# Sche.net
KiCad netlist of a schematic drawn in Altium Designer
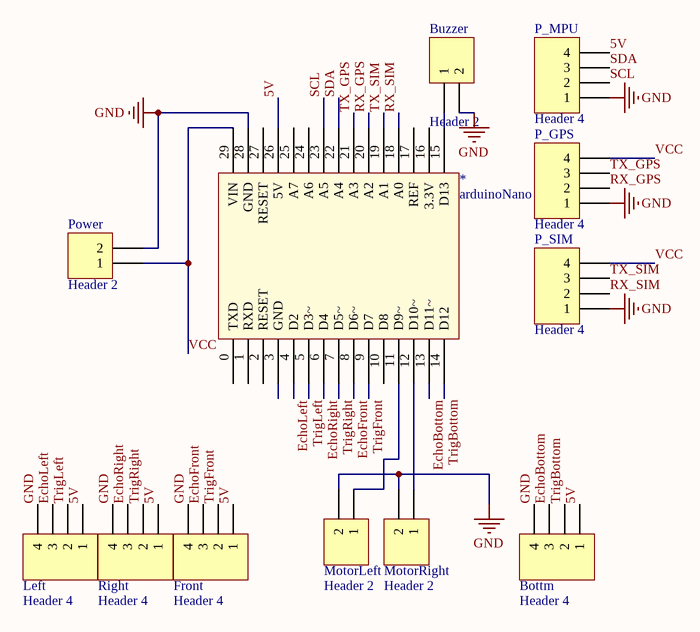
[diagram p0: Sche.SchDoc]

(export (version "E")
  (design (tool "Eeschema 10.0.6"))
  (components
    (comp (ref "*")
      (value "arduinoNano")
      (footprint "Arduino nano")
      (libsource (lib "Duongw_lib") (part "arduinoNano"))
    )
    (comp (ref "Bottm")
      (value "Header 4")
      (footprint "HDR1X4")
      (description "Header, 4-Pin")
      (fields (field (name "PUBLISHER") "Altium Limited"))
      (libsource (lib "") (part "Header 4_1"))
    )
    (comp (ref "Buzzer")
      (value "Header 2")
      (footprint "HDR1X2")
      (description "Header, 2-Pin")
      (fields (field (name "PUBLISHER") "Altium Limited"))
      (libsource (lib "") (part "Header 2_2"))
    )
    (comp (ref "Front")
      (value "Header 4")
      (footprint "HDR1X4")
      (description "Header, 4-Pin")
      (fields (field (name "PUBLISHER") "Altium Limited"))
      (libsource (lib "") (part "Header 4_1"))
    )
    (comp (ref "Left")
      (value "Header 4")
      (footprint "HDR1X4")
      (description "Header, 4-Pin")
      (fields (field (name "PUBLISHER") "Altium Limited"))
      (libsource (lib "") (part "Header 4_1"))
    )
    (comp (ref "MotorLeft")
      (value "Header 2")
      (footprint "HDR1X2")
      (description "Header, 2-Pin")
      (fields (field (name "PUBLISHER") "Altium Limited"))
      (libsource (lib "Miscellaneous Connectors") (part "Header 2"))
    )
    (comp (ref "MotorRight")
      (value "Header 2")
      (footprint "HDR1X2")
      (description "Header, 2-Pin")
      (fields (field (name "PUBLISHER") "Altium Limited"))
      (libsource (lib "Miscellaneous Connectors") (part "Header 2"))
    )
    (comp (ref "Power")
      (value "Header 2")
      (footprint "HDR1X2")
      (description "Header, 2-Pin")
      (fields (field (name "PUBLISHER") "Altium Limited"))
      (libsource (lib "") (part "Header 2_1"))
    )
    (comp (ref "P_GPS")
      (value "Header 4")
      (footprint "HDR1X4")
      (description "Header, 4-Pin")
      (fields (field (name "PUBLISHER") "Altium Limited"))
      (libsource (lib "Miscellaneous Connectors") (part "Header 4"))
    )
    (comp (ref "P_MPU")
      (value "Header 4")
      (footprint "HDR1X4")
      (description "Header, 4-Pin")
      (fields (field (name "PUBLISHER") "Altium Limited"))
      (libsource (lib "Miscellaneous Connectors") (part "Header 4"))
    )
    (comp (ref "P_SIM")
      (value "Header 4")
      (footprint "HDR1X4")
      (description "Header, 4-Pin")
      (fields (field (name "PUBLISHER") "Altium Limited"))
      (libsource (lib "Miscellaneous Connectors") (part "Header 4"))
    )
    (comp (ref "Right")
      (value "Header 4")
      (footprint "HDR1X4")
      (description "Header, 4-Pin")
      (fields (field (name "PUBLISHER") "Altium Limited"))
      (libsource (lib "") (part "Header 4_1"))
    )
  )
  (nets
    (net (code "1") (name "/5V") (class "Default")
      (node (ref "*") (pin "26") (pinfunction "5V_26") (pintype "passive"))
      (node (ref "Bottm") (pin "1") (pinfunction "1_1") (pintype "passive"))
      (node (ref "Front") (pin "1") (pinfunction "1_1") (pintype "passive"))
      (node (ref "Left") (pin "1") (pinfunction "1_1") (pintype "passive"))
      (node (ref "P_MPU") (pin "4") (pinfunction "4_4") (pintype "passive"))
      (node (ref "Right") (pin "1") (pinfunction "1_1") (pintype "passive"))
    )
    (net (code "2") (name "/EchoBottom") (class "Default")
      (node (ref "*") (pin "13") (pinfunction "D11~_13") (pintype "passive"))
      (node (ref "Bottm") (pin "3") (pinfunction "3_3") (pintype "passive"))
    )
    (net (code "3") (name "/EchoFront") (class "Default")
      (node (ref "*") (pin "8") (pinfunction "D6~_8") (pintype "passive"))
      (node (ref "Front") (pin "3") (pinfunction "3_3") (pintype "passive"))
    )
    (net (code "4") (name "/EchoLeft") (class "Default")
      (node (ref "*") (pin "4") (pinfunction "D2_4") (pintype "passive"))
      (node (ref "Left") (pin "3") (pinfunction "3_3") (pintype "passive"))
    )
    (net (code "5") (name "/EchoRight") (class "Default")
      (node (ref "*") (pin "6") (pinfunction "D4_6") (pintype "passive"))
      (node (ref "Right") (pin "3") (pinfunction "3_3") (pintype "passive"))
    )
    (net (code "6") (name "/RX_GPS") (class "Default")
      (node (ref "*") (pin "20") (pinfunction "A2_20") (pintype "passive"))
      (node (ref "P_GPS") (pin "2") (pinfunction "2_2") (pintype "passive"))
    )
    (net (code "7") (name "/RX_SIM") (class "Default")
      (node (ref "*") (pin "18") (pinfunction "A0_18") (pintype "passive"))
      (node (ref "P_SIM") (pin "2") (pinfunction "2_2") (pintype "passive"))
    )
    (net (code "8") (name "/SCL") (class "Default")
      (node (ref "*") (pin "23") (pinfunction "A5_23") (pintype "passive"))
      (node (ref "P_MPU") (pin "2") (pinfunction "2_2") (pintype "passive"))
    )
    (net (code "9") (name "/SDA") (class "Default")
      (node (ref "*") (pin "22") (pinfunction "A4_22") (pintype "passive"))
      (node (ref "P_MPU") (pin "3") (pinfunction "3_3") (pintype "passive"))
    )
    (net (code "10") (name "/TX_GPS") (class "Default")
      (node (ref "*") (pin "21") (pinfunction "A3_21") (pintype "passive"))
      (node (ref "P_GPS") (pin "3") (pinfunction "3_3") (pintype "passive"))
    )
    (net (code "11") (name "/TX_SIM") (class "Default")
      (node (ref "*") (pin "19") (pinfunction "A1_19") (pintype "passive"))
      (node (ref "P_SIM") (pin "3") (pinfunction "3_3") (pintype "passive"))
    )
    (net (code "12") (name "/TrigBottom") (class "Default")
      (node (ref "*") (pin "14") (pinfunction "D12_14") (pintype "passive"))
      (node (ref "Bottm") (pin "2") (pinfunction "2_2") (pintype "passive"))
    )
    (net (code "13") (name "/TrigFront") (class "Default")
      (node (ref "*") (pin "9") (pinfunction "D7_9") (pintype "passive"))
      (node (ref "Front") (pin "2") (pinfunction "2_2") (pintype "passive"))
    )
    (net (code "14") (name "/TrigLeft") (class "Default")
      (node (ref "*") (pin "5") (pinfunction "D3~_5") (pintype "passive"))
      (node (ref "Left") (pin "2") (pinfunction "2_2") (pintype "passive"))
    )
    (net (code "15") (name "/TrigRight") (class "Default")
      (node (ref "*") (pin "7") (pinfunction "D5~_7") (pintype "passive"))
      (node (ref "Right") (pin "2") (pinfunction "2_2") (pintype "passive"))
    )
    (net (code "16") (name "/VCC") (class "Default")
      (node (ref "*") (pin "29") (pinfunction "VIN_29") (pintype "passive"))
      (node (ref "P_GPS") (pin "4") (pinfunction "4_4") (pintype "passive"))
      (node (ref "P_SIM") (pin "4") (pinfunction "4_4") (pintype "passive"))
      (node (ref "Power") (pin "1") (pinfunction "1_1") (pintype "passive"))
    )
    (net (code "17") (name "GND") (class "Default")
      (node (ref "*") (pin "28") (pinfunction "GND_28") (pintype "passive"))
      (node (ref "Bottm") (pin "4") (pinfunction "4_4") (pintype "passive"))
      (node (ref "Buzzer") (pin "2") (pinfunction "2_2") (pintype "passive"))
      (node (ref "Front") (pin "4") (pinfunction "4_4") (pintype "passive"))
      (node (ref "Left") (pin "4") (pinfunction "4_4") (pintype "passive"))
      (node (ref "MotorLeft") (pin "2") (pinfunction "2_2") (pintype "passive"))
      (node (ref "MotorRight") (pin "2") (pinfunction "2_2") (pintype "passive"))
      (node (ref "P_GPS") (pin "1") (pinfunction "1_1") (pintype "passive"))
      (node (ref "P_MPU") (pin "1") (pinfunction "1_1") (pintype "passive"))
      (node (ref "P_SIM") (pin "1") (pinfunction "1_1") (pintype "passive"))
      (node (ref "Power") (pin "2") (pinfunction "2_2") (pintype "passive"))
      (node (ref "Right") (pin "4") (pinfunction "4_4") (pintype "passive"))
    )
    (net (code "18") (name "Net-(*-D9~)") (class "Default")
      (node (ref "*") (pin "11") (pinfunction "D9~_11") (pintype "passive"))
      (node (ref "MotorLeft") (pin "1") (pinfunction "1_1") (pintype "passive"))
    )
    (net (code "19") (name "Net-(*-D10~)") (class "Default")
      (node (ref "*") (pin "12") (pinfunction "D10~_12") (pintype "passive"))
      (node (ref "MotorRight") (pin "1") (pinfunction "1_1") (pintype "passive"))
    )
    (net (code "20") (name "Net-(*-D13)") (class "Default")
      (node (ref "*") (pin "15") (pinfunction "D13_15") (pintype "passive"))
      (node (ref "Buzzer") (pin "1") (pinfunction "1_1") (pintype "passive"))
    )
    (net (code "21") (name "unconnected-(*-3.3V-Pad16)") (class "Default")
      (node (ref "*") (pin "16") (pinfunction "3.3V_16") (pintype "passive"))
    )
    (net (code "22") (name "unconnected-(*-A6-Pad24)") (class "Default")
      (node (ref "*") (pin "24") (pinfunction "A6_24") (pintype "passive"))
    )
    (net (code "23") (name "unconnected-(*-A7-Pad25)") (class "Default")
      (node (ref "*") (pin "25") (pinfunction "A7_25") (pintype "passive"))
    )
    (net (code "24") (name "unconnected-(*-D8-Pad10)") (class "Default")
      (node (ref "*") (pin "10") (pinfunction "D8_10") (pintype "passive"))
    )
    (net (code "25") (name "unconnected-(*-GND-Pad3)") (class "Default")
      (node (ref "*") (pin "3") (pinfunction "GND_3") (pintype "passive"))
    )
    (net (code "26") (name "unconnected-(*-REF-Pad17)") (class "Default")
      (node (ref "*") (pin "17") (pinfunction "REF_17") (pintype "passive"))
    )
    (net (code "27") (name "unconnected-(*-RESET-Pad2)") (class "Default")
      (node (ref "*") (pin "2") (pinfunction "RESET_2") (pintype "passive"))
    )
    (net (code "28") (name "unconnected-(*-RESET-Pad27)") (class "Default")
      (node (ref "*") (pin "27") (pinfunction "RESET_27") (pintype "passive"))
    )
    (net (code "29") (name "unconnected-(*-RXD-Pad1)") (class "Default")
      (node (ref "*") (pin "1") (pinfunction "RXD_1") (pintype "passive"))
    )
    (net (code "30") (name "unconnected-(*-TXD-Pad0)") (class "Default")
      (node (ref "*") (pin "0") (pinfunction "TXD_0") (pintype "passive"))
    )
  )
)
